# SDRAM.net
KiCad netlist of a schematic drawn in Altium Designer
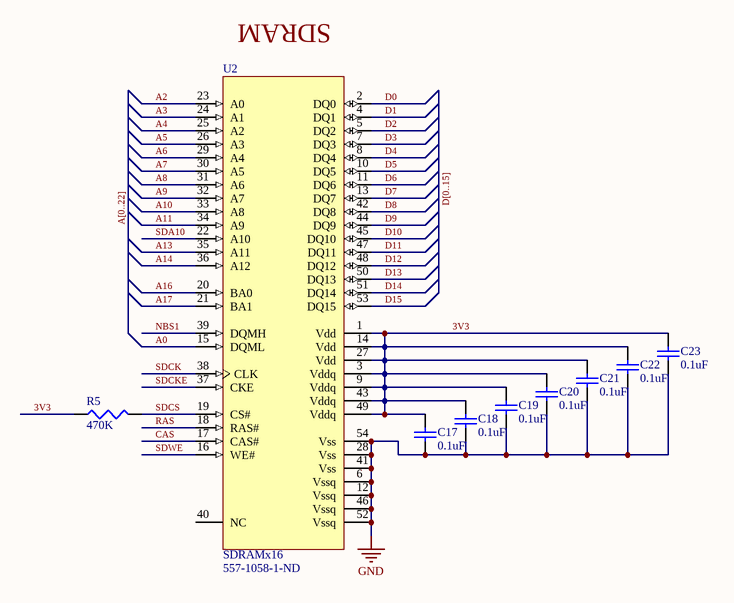
[diagram p0: SDRAM.SchDoc]

(export (version "E")
  (design (tool "Eeschema 10.0.6"))
  (components
    (comp (ref "C17")
      (value "0.1uF")
      (footprint "CAPC2008X06N")
      (description "CAP CER 0.1UF 50V 10% X7R 0805")
      (fields (field (name "Comment") "Kemet_0805_a_0.1uF"))
      (libsource (lib "Capacitors") (part "Kemet_0805_a_0.1uF"))
    )
    (comp (ref "C18")
      (value "0.1uF")
      (footprint "CAPC2008X06N")
      (description "CAP CER 0.1UF 50V 10% X7R 0805")
      (fields (field (name "Comment") "Kemet_0805_a_0.1uF"))
      (libsource (lib "Capacitors") (part "Kemet_0805_a_0.1uF"))
    )
    (comp (ref "C19")
      (value "0.1uF")
      (footprint "CAPC2008X06N")
      (description "CAP CER 0.1UF 50V 10% X7R 0805")
      (fields (field (name "Comment") "Kemet_0805_a_0.1uF"))
      (libsource (lib "Capacitors") (part "Kemet_0805_a_0.1uF"))
    )
    (comp (ref "C20")
      (value "0.1uF")
      (footprint "CAPC2008X06N")
      (description "CAP CER 0.1UF 50V 10% X7R 0805")
      (fields (field (name "Comment") "Kemet_0805_a_0.1uF"))
      (libsource (lib "Capacitors") (part "Kemet_0805_a_0.1uF"))
    )
    (comp (ref "C21")
      (value "0.1uF")
      (footprint "CAPC2008X06N")
      (description "CAP CER 0.1UF 50V 10% X7R 0805")
      (fields (field (name "Comment") "Kemet_0805_a_0.1uF"))
      (libsource (lib "Capacitors") (part "Kemet_0805_a_0.1uF"))
    )
    (comp (ref "C22")
      (value "0.1uF")
      (footprint "CAPC2008X06N")
      (description "CAP CER 0.1UF 50V 10% X7R 0805")
      (fields (field (name "Comment") "Kemet_0805_a_0.1uF"))
      (libsource (lib "Capacitors") (part "Kemet_0805_a_0.1uF"))
    )
    (comp (ref "C23")
      (value "0.1uF")
      (footprint "CAPC2008X06N")
      (description "CAP CER 0.1UF 50V 10% X7R 0805")
      (fields (field (name "Comment") "Kemet_0805_a_0.1uF"))
      (libsource (lib "Capacitors") (part "Kemet_0805_a_0.1uF"))
    )
    (comp (ref "R5")
      (value "470K")
      (footprint "RES0805")
      (description "RES 470K OHM 1/10W .5% 0805 SMD")
      (fields (field (name "Comment") "Susumu_0805_b3_470K"))
      (libsource (lib "Resistors") (part "Susumu_0805_b3_470K"))
    )
    (comp (ref "U2")
      (value "SDRAMx16")
      (footprint "TSOP54")
      (description "SDRAM 54 TSOP II x16 architecture")
      (fields
        (field (name "MANUFACTURER") "Micron Technology INC.")
        (field (name "SUPPLIER PART NUMBER 1") "557-1058-1-ND")
      )
      (libsource (lib "Micron Technology") (part "SDRAMx16"))
    )
  )
  (nets
    (net (code "9") (name "/3V3") (class "Default")
      (node (ref "C17") (pin "2") (pinfunction "2_2") (pintype "passive"))
      (node (ref "C18") (pin "2") (pinfunction "2_2") (pintype "passive"))
      (node (ref "C19") (pin "2") (pinfunction "2_2") (pintype "passive"))
      (node (ref "C20") (pin "2") (pinfunction "2_2") (pintype "passive"))
      (node (ref "C21") (pin "2") (pinfunction "2_2") (pintype "passive"))
      (node (ref "C22") (pin "2") (pinfunction "2_2") (pintype "passive"))
      (node (ref "C23") (pin "2") (pinfunction "2_2") (pintype "passive"))
      (node (ref "R5") (pin "1") (pinfunction "1_1") (pintype "passive"))
      (node (ref "U2") (pin "1") (pinfunction "Vdd_1") (pintype "power_in"))
      (node (ref "U2") (pin "14") (pinfunction "Vdd_14") (pintype "power_in"))
      (node (ref "U2") (pin "27") (pinfunction "Vdd_27") (pintype "power_in"))
      (node (ref "U2") (pin "3") (pinfunction "Vddq_3") (pintype "power_in"))
      (node (ref "U2") (pin "43") (pinfunction "Vddq_43") (pintype "power_in"))
      (node (ref "U2") (pin "49") (pinfunction "Vddq_49") (pintype "power_in"))
      (node (ref "U2") (pin "9") (pinfunction "Vddq_9") (pintype "power_in"))
    )
    (net (code "10") (name "/A0") (class "Default")
      (node (ref "U2") (pin "15") (pinfunction "DQML_15") (pintype "input"))
    )
    (net (code "11") (name "/A2") (class "Default")
      (node (ref "U2") (pin "23") (pinfunction "A0_23") (pintype "input"))
    )
    (net (code "12") (name "/A3") (class "Default")
      (node (ref "U2") (pin "24") (pinfunction "A1_24") (pintype "input"))
    )
    (net (code "13") (name "/A4") (class "Default")
      (node (ref "U2") (pin "25") (pinfunction "A2_25") (pintype "input"))
    )
    (net (code "14") (name "/A5") (class "Default")
      (node (ref "U2") (pin "26") (pinfunction "A3_26") (pintype "input"))
    )
    (net (code "15") (name "/A6") (class "Default")
      (node (ref "U2") (pin "29") (pinfunction "A4_29") (pintype "input"))
    )
    (net (code "16") (name "/A7") (class "Default")
      (node (ref "U2") (pin "30") (pinfunction "A5_30") (pintype "input"))
    )
    (net (code "17") (name "/A8") (class "Default")
      (node (ref "U2") (pin "31") (pinfunction "A6_31") (pintype "input"))
    )
    (net (code "18") (name "/A9") (class "Default")
      (node (ref "U2") (pin "32") (pinfunction "A7_32") (pintype "input"))
    )
    (net (code "19") (name "/A10") (class "Default")
      (node (ref "U2") (pin "33") (pinfunction "A8_33") (pintype "input"))
    )
    (net (code "20") (name "/A11") (class "Default")
      (node (ref "U2") (pin "34") (pinfunction "A9_34") (pintype "input"))
    )
    (net (code "21") (name "/A13") (class "Default")
      (node (ref "U2") (pin "35") (pinfunction "A11_35") (pintype "input"))
    )
    (net (code "22") (name "/A14") (class "Default")
      (node (ref "U2") (pin "36") (pinfunction "A12_36") (pintype "input"))
    )
    (net (code "23") (name "/A16") (class "Default")
      (node (ref "U2") (pin "20") (pinfunction "BA0_20") (pintype "input"))
    )
    (net (code "24") (name "/A17") (class "Default")
      (node (ref "U2") (pin "21") (pinfunction "BA1_21") (pintype "input"))
    )
    (net (code "26") (name "/CAS") (class "Default")
      (node (ref "U2") (pin "17") (pinfunction "CAS#_17") (pintype "input"))
    )
    (net (code "27") (name "/D0") (class "Default")
      (node (ref "U2") (pin "2") (pinfunction "DQ0_2") (pintype "bidirectional"))
    )
    (net (code "28") (name "/D1") (class "Default")
      (node (ref "U2") (pin "4") (pinfunction "DQ1_4") (pintype "bidirectional"))
    )
    (net (code "29") (name "/D2") (class "Default")
      (node (ref "U2") (pin "5") (pinfunction "DQ2_5") (pintype "bidirectional"))
    )
    (net (code "30") (name "/D3") (class "Default")
      (node (ref "U2") (pin "7") (pinfunction "DQ3_7") (pintype "bidirectional"))
    )
    (net (code "31") (name "/D4") (class "Default")
      (node (ref "U2") (pin "8") (pinfunction "DQ4_8") (pintype "bidirectional"))
    )
    (net (code "32") (name "/D5") (class "Default")
      (node (ref "U2") (pin "10") (pinfunction "DQ5_10") (pintype "bidirectional"))
    )
    (net (code "33") (name "/D6") (class "Default")
      (node (ref "U2") (pin "11") (pinfunction "DQ6_11") (pintype "bidirectional"))
    )
    (net (code "34") (name "/D7") (class "Default")
      (node (ref "U2") (pin "13") (pinfunction "DQ7_13") (pintype "bidirectional"))
    )
    (net (code "35") (name "/D8") (class "Default")
      (node (ref "U2") (pin "42") (pinfunction "DQ8_42") (pintype "bidirectional"))
    )
    (net (code "36") (name "/D9") (class "Default")
      (node (ref "U2") (pin "44") (pinfunction "DQ9_44") (pintype "bidirectional"))
    )
    (net (code "37") (name "/D10") (class "Default")
      (node (ref "U2") (pin "45") (pinfunction "DQ10_45") (pintype "bidirectional"))
    )
    (net (code "38") (name "/D11") (class "Default")
      (node (ref "U2") (pin "47") (pinfunction "DQ11_47") (pintype "bidirectional"))
    )
    (net (code "39") (name "/D12") (class "Default")
      (node (ref "U2") (pin "48") (pinfunction "DQ12_48") (pintype "bidirectional"))
    )
    (net (code "40") (name "/D13") (class "Default")
      (node (ref "U2") (pin "50") (pinfunction "DQ13_50") (pintype "bidirectional"))
    )
    (net (code "41") (name "/D14") (class "Default")
      (node (ref "U2") (pin "51") (pinfunction "DQ14_51") (pintype "bidirectional"))
    )
    (net (code "42") (name "/D15") (class "Default")
      (node (ref "U2") (pin "53") (pinfunction "DQ15_53") (pintype "bidirectional"))
    )
    (net (code "44") (name "/NBS1") (class "Default")
      (node (ref "U2") (pin "39") (pinfunction "DQMH_39") (pintype "input"))
    )
    (net (code "45") (name "/RAS") (class "Default")
      (node (ref "U2") (pin "18") (pinfunction "RAS#_18") (pintype "input"))
    )
    (net (code "46") (name "/SDA10") (class "Default")
      (node (ref "U2") (pin "22") (pinfunction "A10_22") (pintype "input"))
    )
    (net (code "47") (name "/SDCK") (class "Default")
      (node (ref "U2") (pin "38") (pinfunction "CLK_38") (pintype "input"))
    )
    (net (code "48") (name "/SDCKE") (class "Default")
      (node (ref "U2") (pin "37") (pinfunction "CKE_37") (pintype "input"))
    )
    (net (code "49") (name "/SDCS") (class "Default")
      (node (ref "R5") (pin "2") (pinfunction "2_2") (pintype "passive"))
      (node (ref "U2") (pin "19") (pinfunction "CS#_19") (pintype "input"))
    )
    (net (code "50") (name "/SDWE") (class "Default")
      (node (ref "U2") (pin "16") (pinfunction "WE#_16") (pintype "input"))
    )
    (net (code "51") (name "GND") (class "Default")
      (node (ref "C17") (pin "1") (pinfunction "1_1") (pintype "passive"))
      (node (ref "C18") (pin "1") (pinfunction "1_1") (pintype "passive"))
      (node (ref "C19") (pin "1") (pinfunction "1_1") (pintype "passive"))
      (node (ref "C20") (pin "1") (pinfunction "1_1") (pintype "passive"))
      (node (ref "C21") (pin "1") (pinfunction "1_1") (pintype "passive"))
      (node (ref "C22") (pin "1") (pinfunction "1_1") (pintype "passive"))
      (node (ref "C23") (pin "1") (pinfunction "1_1") (pintype "passive"))
      (node (ref "U2") (pin "12") (pinfunction "Vssq_12") (pintype "power_in"))
      (node (ref "U2") (pin "28") (pinfunction "Vss_28") (pintype "power_in"))
      (node (ref "U2") (pin "41") (pinfunction "Vss_41") (pintype "power_in"))
      (node (ref "U2") (pin "46") (pinfunction "Vssq_46") (pintype "power_in"))
      (node (ref "U2") (pin "52") (pinfunction "Vssq_52") (pintype "power_in"))
      (node (ref "U2") (pin "54") (pinfunction "Vss_54") (pintype "power_in"))
      (node (ref "U2") (pin "6") (pinfunction "Vssq_6") (pintype "power_in"))
    )
    (net (code "52") (name "unconnected-(U2-NC-Pad40)") (class "Default")
      (node (ref "U2") (pin "40") (pinfunction "NC_40") (pintype "passive"))
    )
  )
)
